# Power.net
KiCad netlist of a schematic drawn in Altium Designer
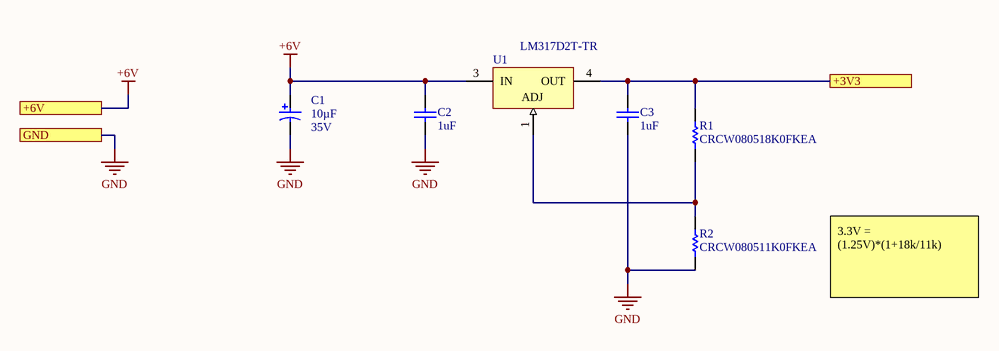
[diagram p0: Power.SchDoc]

(export (version "E")
  (design (tool "Eeschema 10.0.6"))
  (components
    (comp (ref "C1")
      (value "EEE-FK1V100UR")
      (footprint "PNSC-FK-V-B_V")
      (fields
        (field (name "RATED VOLTAGE") "35V")
        (field (name "MANUFACTURER") "Panasonic")
        (field (name "CAPACITANCE") "10µF")
      )
      (libsource (lib "Altium Content Vault") (part "CAP-P-2"))
    )
    (comp (ref "C2")
      (value "1uF")
      (footprint "CAPC2013X100X50NL20T25")
      (fields (field (name "PART NUMBER") "C0805X105K3RACTU") (field (name "MANUFACTURER") "Kemet"))
      (libsource (lib "Altium Content Vault") (part "CAP"))
    )
    (comp (ref "C3")
      (value "1uF")
      (footprint "CAPC2013X100X50NL20T25")
      (fields (field (name "PART NUMBER") "C0805X105K3RACTU") (field (name "MANUFACTURER") "Kemet"))
      (libsource (lib "Altium Content Vault") (part "CAP"))
    )
    (comp (ref "R1")
      (value "CRCW080518K0FKEA")
      (footprint "RESC2013X50X30NL20T20")
      (fields (field (name "MANUFACTURER") "Vishay Dale"))
      (libsource (lib "Altium Content Vault") (part "RES"))
    )
    (comp (ref "R2")
      (value "CRCW080511K0FKEA")
      (footprint "RESC2013X50X30NL20T20")
      (fields (field (name "MANUFACTURER") "Vishay Dale"))
      (libsource (lib "Altium Content Vault") (part "RES"))
    )
    (comp (ref "U1")
      (value "LM317D2T-TR")
      (footprint "TO-263_N")
      (description "1.5A, 1.2V to 37V Adjustable Voltage Regulator, 3-Pin D2PAK, Tape and Reel")
      (libsource (lib "Altium Content Vault") (part "PM-REG-217-SOT3"))
    )
  )
  (nets
    (net (code "1") (name "+6V") (class "Default")
      (node (ref "C1") (pin "1") (pinfunction "1_1") (pintype "passive"))
      (node (ref "C2") (pin "2") (pinfunction "2_2") (pintype "passive"))
      (node (ref "U1") (pin "3") (pinfunction "IN_3") (pintype "power_in"))
    )
    (net (code "2") (name "/+3V3") (class "Default")
      (node (ref "C3") (pin "2") (pinfunction "2_2") (pintype "passive"))
      (node (ref "R1") (pin "2") (pinfunction "2_2") (pintype "passive"))
      (node (ref "U1") (pin "4") (pinfunction "OUT_4") (pintype "power_in"))
    )
    (net (code "3") (name "GND") (class "Default")
      (node (ref "C1") (pin "2") (pinfunction "2_2") (pintype "passive"))
      (node (ref "C2") (pin "1") (pinfunction "1_1") (pintype "passive"))
      (node (ref "C3") (pin "1") (pinfunction "1_1") (pintype "passive"))
      (node (ref "R2") (pin "1") (pinfunction "1_1") (pintype "passive"))
    )
    (net (code "4") (name "Net-(U1-ADJ)") (class "Default")
      (node (ref "R1") (pin "1") (pinfunction "1_1") (pintype "passive"))
      (node (ref "R2") (pin "2") (pinfunction "2_2") (pintype "passive"))
      (node (ref "U1") (pin "1") (pinfunction "ADJ_1") (pintype "input"))
    )
  )
)
